# 3_Codec.net
KiCad netlist of a schematic drawn in Altium Designer
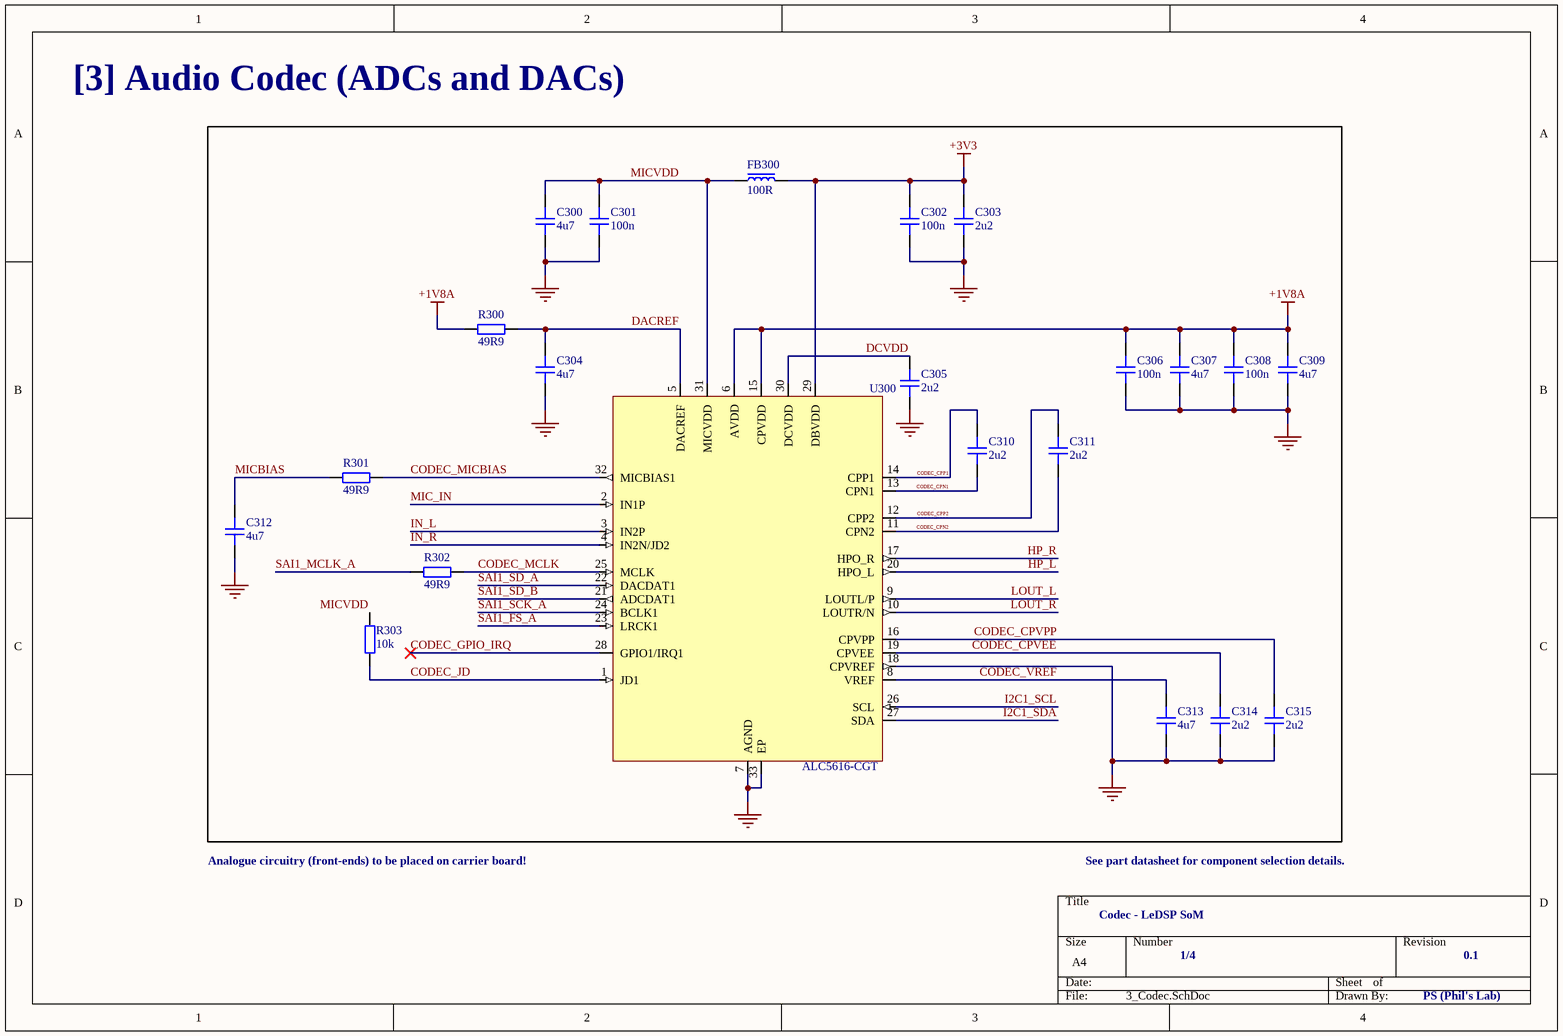
[diagram p0: 3_Codec.SchDoc]

(export (version "E")
  (design (tool "Eeschema 10.0.6"))
  (components
    (comp (ref "C300")
      (value "4u7")
      (footprint "CAP_0402")
      (description "Capacitor SMD 0402 16V")
      (libsource (lib "Schematic-Lib-PhilsLab") (part "CAP_0402_16V"))
    )
    (comp (ref "C301")
      (value "100n")
      (footprint "CAP_0402")
      (description "Capacitor SMD 0402 16V")
      (libsource (lib "Schematic-Lib-PhilsLab") (part "CAP_0402_16V"))
    )
    (comp (ref "C302")
      (value "100n")
      (footprint "CAP_0402")
      (description "Capacitor SMD 0402 16V")
      (libsource (lib "Schematic-Lib-PhilsLab") (part "CAP_0402_16V"))
    )
    (comp (ref "C303")
      (value "2u2")
      (footprint "CAP_0402")
      (description "Capacitor SMD 0402 16V")
      (libsource (lib "Schematic-Lib-PhilsLab") (part "CAP_0402_16V"))
    )
    (comp (ref "C304")
      (value "4u7")
      (footprint "CAP_0402")
      (description "Capacitor SMD 0402 16V")
      (libsource (lib "Schematic-Lib-PhilsLab") (part "CAP_0402_16V"))
    )
    (comp (ref "C305")
      (value "2u2")
      (footprint "CAP_0402")
      (description "Capacitor SMD 0402 16V")
      (libsource (lib "Schematic-Lib-PhilsLab") (part "CAP_0402_16V"))
    )
    (comp (ref "C306")
      (value "100n")
      (footprint "CAP_0402")
      (description "Capacitor SMD 0402 16V")
      (libsource (lib "Schematic-Lib-PhilsLab") (part "CAP_0402_16V"))
    )
    (comp (ref "C307")
      (value "4u7")
      (footprint "CAP_0402")
      (description "Capacitor SMD 0402 16V")
      (libsource (lib "Schematic-Lib-PhilsLab") (part "CAP_0402_16V"))
    )
    (comp (ref "C308")
      (value "100n")
      (footprint "CAP_0402")
      (description "Capacitor SMD 0402 16V")
      (libsource (lib "Schematic-Lib-PhilsLab") (part "CAP_0402_16V"))
    )
    (comp (ref "C309")
      (value "4u7")
      (footprint "CAP_0402")
      (description "Capacitor SMD 0402 16V")
      (libsource (lib "Schematic-Lib-PhilsLab") (part "CAP_0402_16V"))
    )
    (comp (ref "C310")
      (value "2u2")
      (footprint "CAP_0402")
      (description "Capacitor SMD 0402 16V")
      (libsource (lib "Schematic-Lib-PhilsLab") (part "CAP_0402_16V"))
    )
    (comp (ref "C311")
      (value "2u2")
      (footprint "CAP_0402")
      (description "Capacitor SMD 0402 16V")
      (libsource (lib "Schematic-Lib-PhilsLab") (part "CAP_0402_16V"))
    )
    (comp (ref "C312")
      (value "4u7")
      (footprint "CAP_0402")
      (description "Capacitor SMD 0402 16V")
      (libsource (lib "Schematic-Lib-PhilsLab") (part "CAP_0402_16V"))
    )
    (comp (ref "C313")
      (value "4u7")
      (footprint "CAP_0402")
      (description "Capacitor SMD 0402 16V")
      (libsource (lib "Schematic-Lib-PhilsLab") (part "CAP_0402_16V"))
    )
    (comp (ref "C314")
      (value "2u2")
      (footprint "CAP_0402")
      (description "Capacitor SMD 0402 16V")
      (libsource (lib "Schematic-Lib-PhilsLab") (part "CAP_0402_16V"))
    )
    (comp (ref "C315")
      (value "2u2")
      (footprint "CAP_0402")
      (description "Capacitor SMD 0402 16V")
      (libsource (lib "Schematic-Lib-PhilsLab") (part "CAP_0402_16V"))
    )
    (comp (ref "FB300")
      (value "100R")
      (footprint "FB_0603")
      (description "Ferrite Bead SMD 0603")
      (libsource (lib "Schematic-Lib-PhilsLab") (part "FB_0603"))
    )
    (comp (ref "R300")
      (value "49R9")
      (footprint "RES_0402")
      (description "Resistor SMD 0402")
      (libsource (lib "Schematic-Lib-PhilsLab") (part "RES_0402"))
    )
    (comp (ref "R301")
      (value "49R9")
      (footprint "RES_0402")
      (description "Resistor SMD 0402")
      (libsource (lib "Schematic-Lib-PhilsLab") (part "RES_0402"))
    )
    (comp (ref "R302")
      (value "49R9")
      (footprint "RES_0402")
      (description "Resistor SMD 0402")
      (libsource (lib "Schematic-Lib-PhilsLab") (part "RES_0402"))
    )
    (comp (ref "R303")
      (value "10k")
      (footprint "RES_0402")
      (description "Resistor SMD 0402")
      (libsource (lib "Schematic-Lib-PhilsLab") (part "RES_0402"))
    )
    (comp (ref "U300")
      (value "ALC5616-CGT")
      (footprint "QFN-32-4x4")
      (description "Ultra-Low Power Audio CODEC")
      (fields (field (name "MANUFACTURER") "Realtek"))
      (libsource (lib "Schematic-Lib-PhilsLab") (part "ALC5616-CGT"))
    )
  )
  (nets
    (net (code "1") (name "+1V8A") (class "Default")
      (node (ref "C306") (pin "2") (pinfunction "2_2") (pintype "passive"))
      (node (ref "C307") (pin "2") (pinfunction "2_2") (pintype "passive"))
      (node (ref "C308") (pin "2") (pinfunction "2_2") (pintype "passive"))
      (node (ref "C309") (pin "2") (pinfunction "2_2") (pintype "passive"))
      (node (ref "R300") (pin "1") (pinfunction "1_1") (pintype "passive"))
      (node (ref "U300") (pin "15") (pinfunction "CPVDD_15") (pintype "power_in"))
      (node (ref "U300") (pin "6") (pinfunction "AVDD_6") (pintype "power_in"))
    )
    (net (code "2") (name "+3V3") (class "Default")
      (node (ref "C302") (pin "2") (pinfunction "2_2") (pintype "passive"))
      (node (ref "C303") (pin "2") (pinfunction "2_2") (pintype "passive"))
      (node (ref "FB300") (pin "2") (pinfunction "2_2") (pintype "passive"))
      (node (ref "U300") (pin "29") (pinfunction "DBVDD_29") (pintype "power_in"))
    )
    (net (code "3") (name "/CODEC_CPN1") (class "Default")
      (node (ref "C310") (pin "1") (pinfunction "1_1") (pintype "passive"))
      (node (ref "U300") (pin "13") (pinfunction "CPN1_13") (pintype "power_in"))
    )
    (net (code "4") (name "/CODEC_CPN2") (class "Default")
      (node (ref "C311") (pin "1") (pinfunction "1_1") (pintype "passive"))
      (node (ref "U300") (pin "11") (pinfunction "CPN2_11") (pintype "power_in"))
    )
    (net (code "5") (name "/CODEC_CPP1") (class "Default")
      (node (ref "C310") (pin "2") (pinfunction "2_2") (pintype "passive"))
      (node (ref "U300") (pin "14") (pinfunction "CPP1_14") (pintype "power_in"))
    )
    (net (code "6") (name "/CODEC_CPP2") (class "Default")
      (node (ref "C311") (pin "2") (pinfunction "2_2") (pintype "passive"))
      (node (ref "U300") (pin "12") (pinfunction "CPP2_12") (pintype "power_in"))
    )
    (net (code "7") (name "/CODEC_CPVEE") (class "Default")
      (node (ref "C314") (pin "2") (pinfunction "2_2") (pintype "passive"))
      (node (ref "U300") (pin "19") (pinfunction "CPVEE_19") (pintype "passive"))
    )
    (net (code "8") (name "/CODEC_CPVPP") (class "Default")
      (node (ref "C315") (pin "2") (pinfunction "2_2") (pintype "passive"))
      (node (ref "U300") (pin "16") (pinfunction "CPVPP_16") (pintype "passive"))
    )
    (net (code "9") (name "/CODEC_GPIO_IRQ") (class "Default")
      (node (ref "U300") (pin "28") (pinfunction "GPIO1/IRQ1_28") (pintype "bidirectional+no_connect"))
    )
    (net (code "10") (name "/CODEC_JD") (class "Default")
      (node (ref "R303") (pin "1") (pinfunction "1_1") (pintype "passive"))
      (node (ref "U300") (pin "1") (pinfunction "JD1_1") (pintype "input"))
    )
    (net (code "11") (name "/CODEC_MCLK") (class "Default")
      (node (ref "R302") (pin "2") (pinfunction "2_2") (pintype "passive"))
      (node (ref "U300") (pin "25") (pinfunction "MCLK_25") (pintype "input"))
    )
    (net (code "12") (name "/CODEC_MICBIAS") (class "Default")
      (node (ref "R301") (pin "2") (pinfunction "2_2") (pintype "passive"))
      (node (ref "U300") (pin "32") (pinfunction "MICBIAS1_32") (pintype "output"))
    )
    (net (code "13") (name "/CODEC_VREF") (class "Default")
      (node (ref "C313") (pin "2") (pinfunction "2_2") (pintype "passive"))
      (node (ref "U300") (pin "8") (pinfunction "VREF_8") (pintype "power_in"))
    )
    (net (code "14") (name "/DACREF") (class "Default")
      (node (ref "C304") (pin "2") (pinfunction "2_2") (pintype "passive"))
      (node (ref "R300") (pin "2") (pinfunction "2_2") (pintype "passive"))
      (node (ref "U300") (pin "5") (pinfunction "DACREF_5") (pintype "power_in"))
    )
    (net (code "15") (name "/DCVDD") (class "Default")
      (node (ref "C305") (pin "2") (pinfunction "2_2") (pintype "passive"))
      (node (ref "U300") (pin "30") (pinfunction "DCVDD_30") (pintype "power_in"))
    )
    (net (code "16") (name "/HP_L") (class "Default")
      (node (ref "U300") (pin "20") (pinfunction "HPO_L_20") (pintype "output"))
    )
    (net (code "17") (name "/HP_R") (class "Default")
      (node (ref "U300") (pin "17") (pinfunction "HPO_R_17") (pintype "output"))
    )
    (net (code "18") (name "/I2C1_SCL") (class "Default")
      (node (ref "U300") (pin "26") (pinfunction "SCL_26") (pintype "input"))
    )
    (net (code "19") (name "/I2C1_SDA") (class "Default")
      (node (ref "U300") (pin "27") (pinfunction "SDA_27") (pintype "bidirectional"))
    )
    (net (code "20") (name "/IN_L") (class "Default")
      (node (ref "U300") (pin "3") (pinfunction "IN2P_3") (pintype "input"))
    )
    (net (code "21") (name "/IN_R") (class "Default")
      (node (ref "U300") (pin "4") (pinfunction "IN2N/JD2_4") (pintype "input"))
    )
    (net (code "22") (name "/LOUT_L") (class "Default")
      (node (ref "U300") (pin "9") (pinfunction "LOUTL/P_9") (pintype "output"))
    )
    (net (code "23") (name "/LOUT_R") (class "Default")
      (node (ref "U300") (pin "10") (pinfunction "LOUTR/N_10") (pintype "output"))
    )
    (net (code "24") (name "/MICBIAS") (class "Default")
      (node (ref "C312") (pin "2") (pinfunction "2_2") (pintype "passive"))
      (node (ref "R301") (pin "1") (pinfunction "1_1") (pintype "passive"))
    )
    (net (code "25") (name "/MICVDD") (class "Default")
      (node (ref "C300") (pin "2") (pinfunction "2_2") (pintype "passive"))
      (node (ref "C301") (pin "2") (pinfunction "2_2") (pintype "passive"))
      (node (ref "FB300") (pin "1") (pinfunction "1_1") (pintype "passive"))
      (node (ref "R303") (pin "2") (pinfunction "2_2") (pintype "passive"))
      (node (ref "U300") (pin "31") (pinfunction "MICVDD_31") (pintype "power_in"))
    )
    (net (code "26") (name "/MIC_IN") (class "Default")
      (node (ref "U300") (pin "2") (pinfunction "IN1P_2") (pintype "input"))
    )
    (net (code "27") (name "/SAI1_FS_A") (class "Default")
      (node (ref "U300") (pin "23") (pinfunction "LRCK1_23") (pintype "input"))
    )
    (net (code "28") (name "/SAI1_MCLK_A") (class "Default")
      (node (ref "R302") (pin "1") (pinfunction "1_1") (pintype "passive"))
    )
    (net (code "29") (name "/SAI1_SCK_A") (class "Default")
      (node (ref "U300") (pin "24") (pinfunction "BCLK1_24") (pintype "input"))
    )
    (net (code "30") (name "/SAI1_SD_A") (class "Default")
      (node (ref "U300") (pin "22") (pinfunction "DACDAT1_22") (pintype "input"))
    )
    (net (code "31") (name "/SAI1_SD_B") (class "Default")
      (node (ref "U300") (pin "21") (pinfunction "ADCDAT1_21") (pintype "output"))
    )
    (net (code "32") (name "GND") (class "Default")
      (node (ref "C300") (pin "1") (pinfunction "1_1") (pintype "passive"))
      (node (ref "C301") (pin "1") (pinfunction "1_1") (pintype "passive"))
      (node (ref "C302") (pin "1") (pinfunction "1_1") (pintype "passive"))
      (node (ref "C303") (pin "1") (pinfunction "1_1") (pintype "passive"))
      (node (ref "C304") (pin "1") (pinfunction "1_1") (pintype "passive"))
      (node (ref "C305") (pin "1") (pinfunction "1_1") (pintype "passive"))
      (node (ref "C306") (pin "1") (pinfunction "1_1") (pintype "passive"))
      (node (ref "C307") (pin "1") (pinfunction "1_1") (pintype "passive"))
      (node (ref "C308") (pin "1") (pinfunction "1_1") (pintype "passive"))
      (node (ref "C309") (pin "1") (pinfunction "1_1") (pintype "passive"))
      (node (ref "C312") (pin "1") (pinfunction "1_1") (pintype "passive"))
      (node (ref "C313") (pin "1") (pinfunction "1_1") (pintype "passive"))
      (node (ref "C314") (pin "1") (pinfunction "1_1") (pintype "passive"))
      (node (ref "C315") (pin "1") (pinfunction "1_1") (pintype "passive"))
      (node (ref "U300") (pin "18") (pinfunction "CPVREF_18") (pintype "output"))
      (node (ref "U300") (pin "33") (pinfunction "EP_33") (pintype "power_in"))
      (node (ref "U300") (pin "7") (pinfunction "AGND_7") (pintype "power_in"))
    )
  )
)
